# SCH_POTY_2026-03-09.net
KiCad netlist of a schematic drawn in EasyEDA
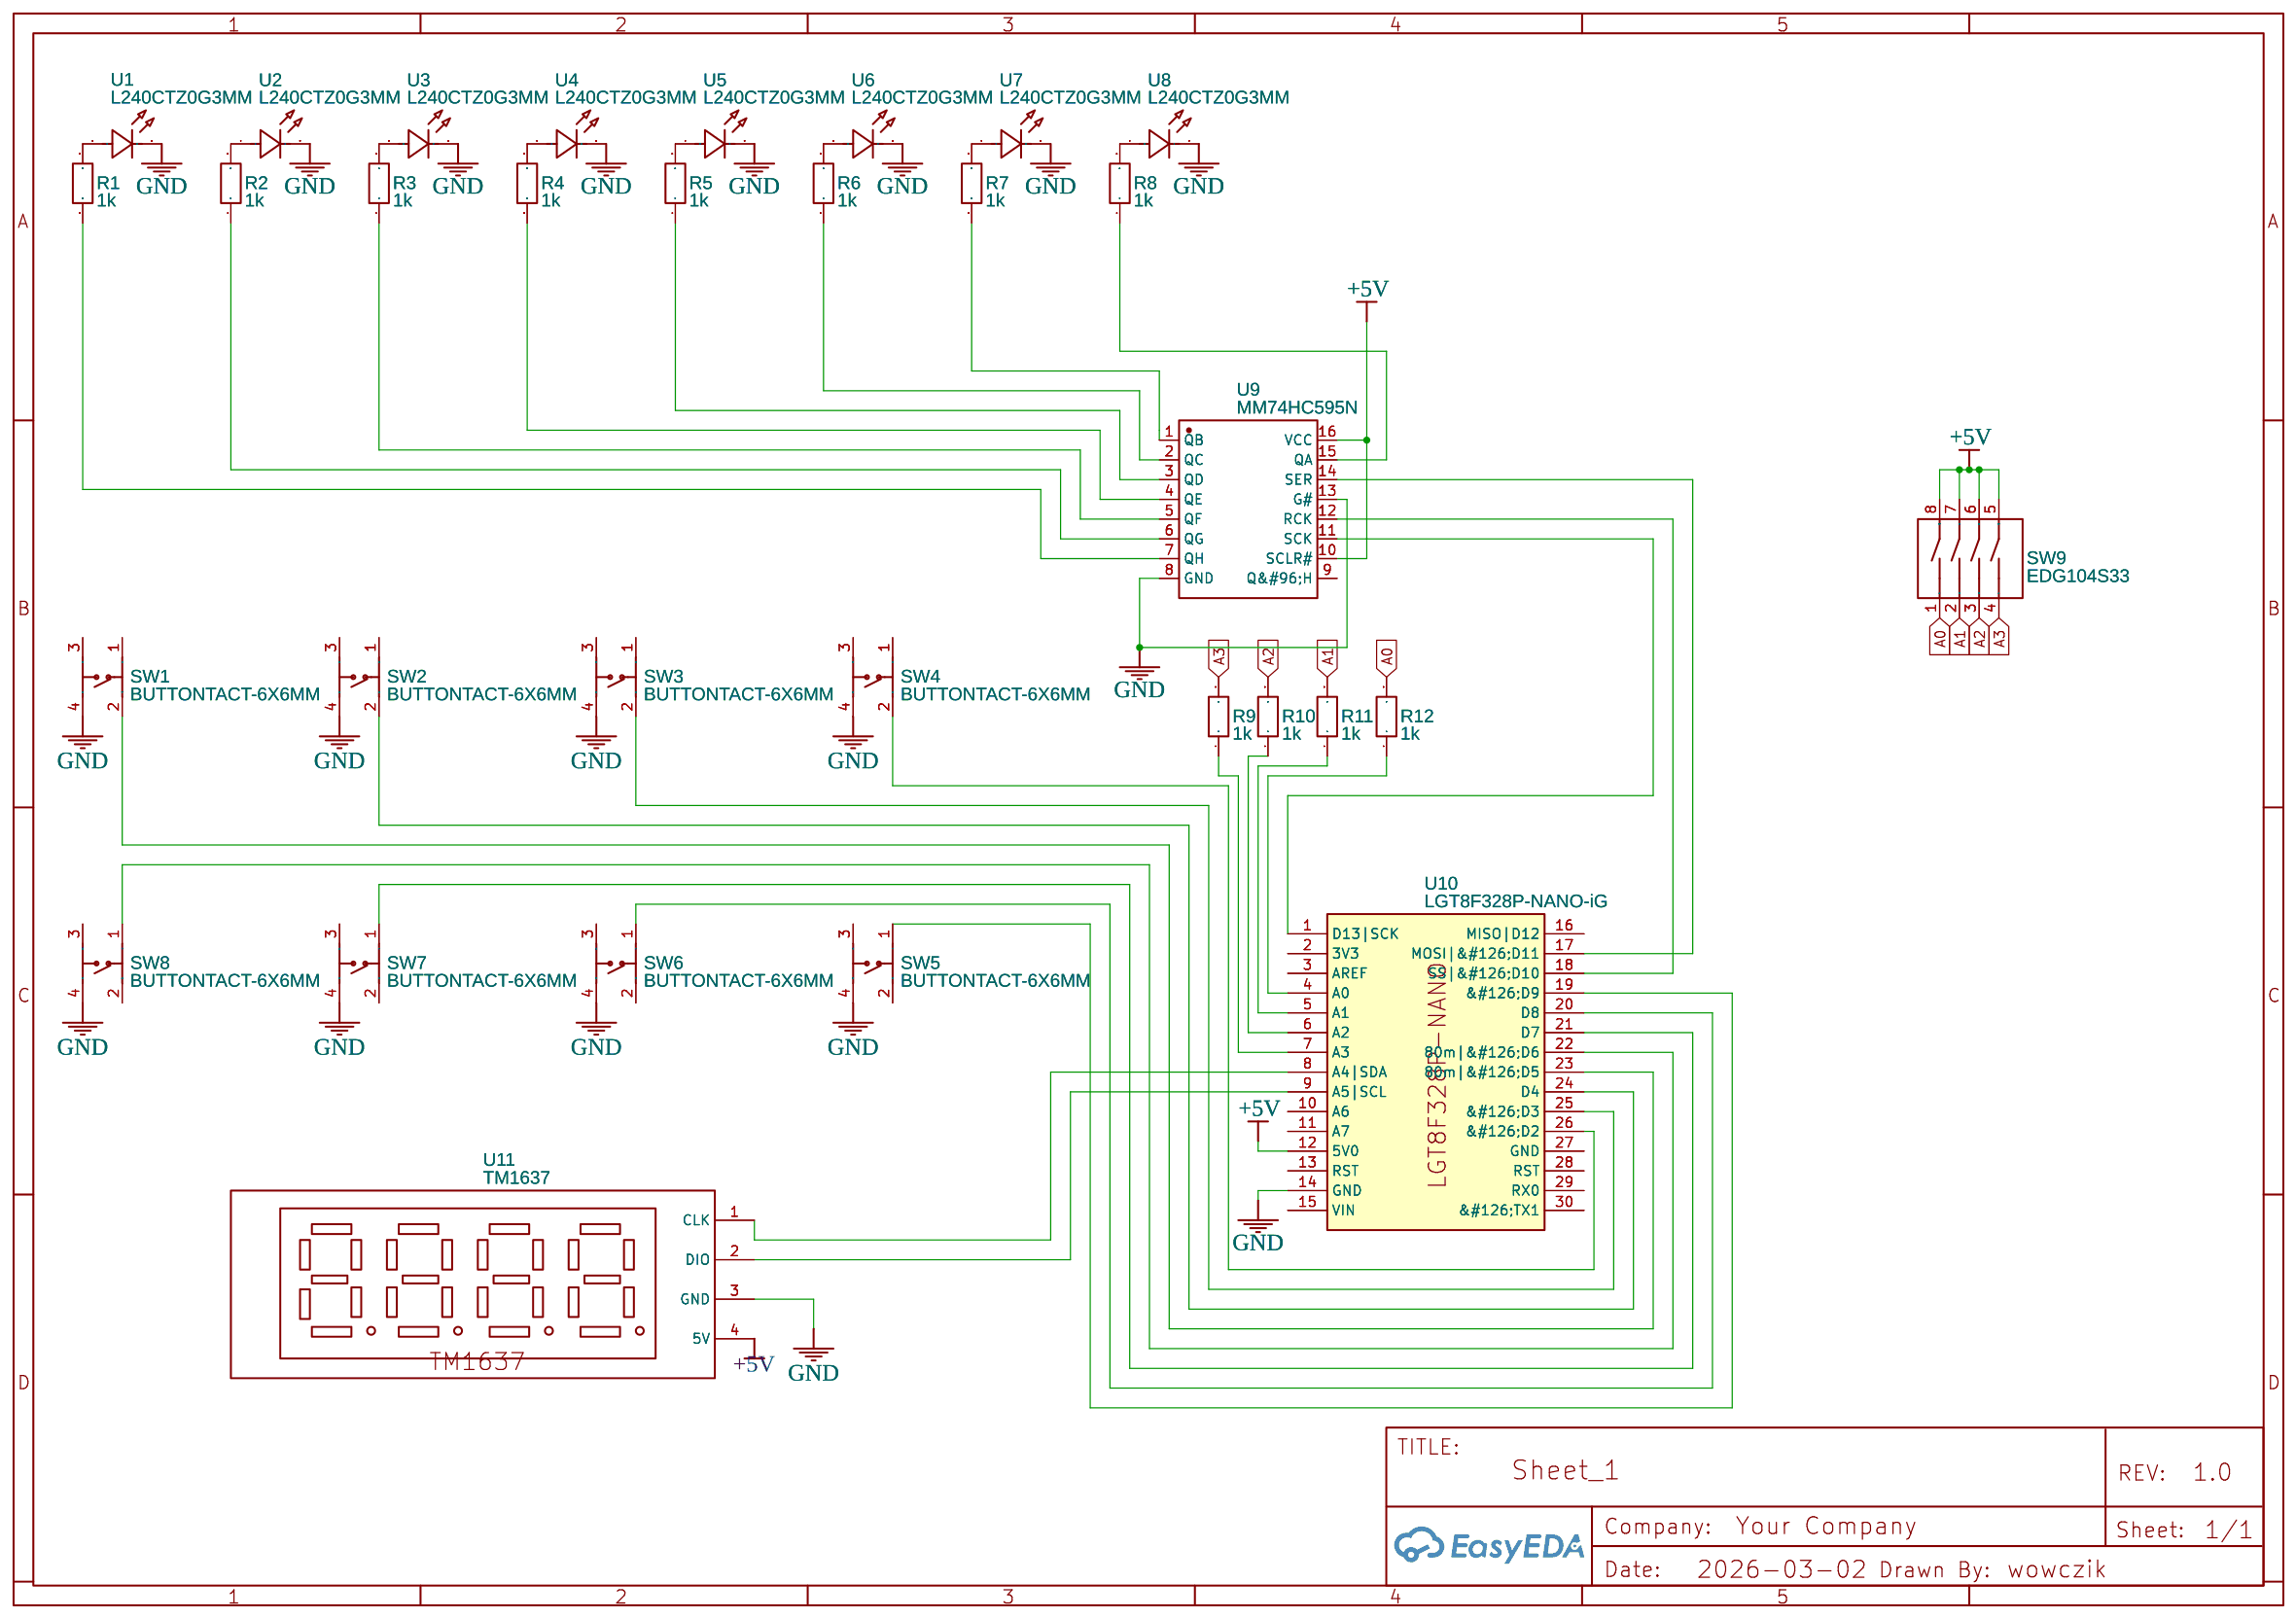
[diagram p0: schematic sheet]

(export (version "E")
  (design (tool "Eeschema 10.0.6"))
  (components
    (comp (ref "R1") (value "1k") (libsource (lib "") (part "R_AXIAL-0.3_EU")))
    (comp (ref "R2") (value "1k") (libsource (lib "") (part "R_AXIAL-0.3_EU")))
    (comp (ref "R3") (value "1k") (libsource (lib "") (part "R_AXIAL-0.3_EU")))
    (comp (ref "R4") (value "1k") (libsource (lib "") (part "R_AXIAL-0.3_EU")))
    (comp (ref "R5") (value "1k") (libsource (lib "") (part "R_AXIAL-0.3_EU")))
    (comp (ref "R6") (value "1k") (libsource (lib "") (part "R_AXIAL-0.3_EU")))
    (comp (ref "R7") (value "1k") (libsource (lib "") (part "R_AXIAL-0.3_EU")))
    (comp (ref "R8") (value "1k") (libsource (lib "") (part "R_AXIAL-0.3_EU")))
    (comp (ref "R9") (value "1k") (libsource (lib "") (part "R_0603_EU")))
    (comp (ref "R10") (value "1k") (libsource (lib "") (part "R_0603_EU")))
    (comp (ref "R11") (value "1k") (libsource (lib "") (part "R_0603_EU")))
    (comp (ref "R12") (value "1k") (libsource (lib "") (part "R_0603_EU")))
    (comp (ref "SW1")
      (value "BUTTONTACT-6X6MM")
      (fields (field (name "Manufacturer Part") "Buttontact-6x6mm"))
      (libsource (lib "") (part "BUTTONTACT-6X6MM"))
    )
    (comp (ref "SW2")
      (value "BUTTONTACT-6X6MM")
      (fields (field (name "Manufacturer Part") "Buttontact-6x6mm"))
      (libsource (lib "") (part "BUTTONTACT-6X6MM"))
    )
    (comp (ref "SW3")
      (value "BUTTONTACT-6X6MM")
      (fields (field (name "Manufacturer Part") "Buttontact-6x6mm"))
      (libsource (lib "") (part "BUTTONTACT-6X6MM"))
    )
    (comp (ref "SW4")
      (value "BUTTONTACT-6X6MM")
      (fields (field (name "Manufacturer Part") "Buttontact-6x6mm"))
      (libsource (lib "") (part "BUTTONTACT-6X6MM"))
    )
    (comp (ref "SW5")
      (value "BUTTONTACT-6X6MM")
      (fields (field (name "Manufacturer Part") "Buttontact-6x6mm"))
      (libsource (lib "") (part "BUTTONTACT-6X6MM"))
    )
    (comp (ref "SW6")
      (value "BUTTONTACT-6X6MM")
      (fields (field (name "Manufacturer Part") "Buttontact-6x6mm"))
      (libsource (lib "") (part "BUTTONTACT-6X6MM"))
    )
    (comp (ref "SW7")
      (value "BUTTONTACT-6X6MM")
      (fields (field (name "Manufacturer Part") "Buttontact-6x6mm"))
      (libsource (lib "") (part "BUTTONTACT-6X6MM"))
    )
    (comp (ref "SW8")
      (value "BUTTONTACT-6X6MM")
      (fields (field (name "Manufacturer Part") "Buttontact-6x6mm"))
      (libsource (lib "") (part "BUTTONTACT-6X6MM"))
    )
    (comp (ref "SW9")
      (value "EDG104S33")
      (fields (field (name "Manufacturer") "ECE(百容)"))
      (libsource (lib "") (part "EDG104S33"))
    )
    (comp (ref "U1") (value "L240CTZ0G3MM") (libsource (lib "") (part "L240CTZ0G3MM")))
    (comp (ref "U2") (value "L240CTZ0G3MM") (libsource (lib "") (part "L240CTZ0G3MM")))
    (comp (ref "U3") (value "L240CTZ0G3MM") (libsource (lib "") (part "L240CTZ0G3MM")))
    (comp (ref "U4") (value "L240CTZ0G3MM") (libsource (lib "") (part "L240CTZ0G3MM")))
    (comp (ref "U5") (value "L240CTZ0G3MM") (libsource (lib "") (part "L240CTZ0G3MM")))
    (comp (ref "U6") (value "L240CTZ0G3MM") (libsource (lib "") (part "L240CTZ0G3MM")))
    (comp (ref "U7") (value "L240CTZ0G3MM") (libsource (lib "") (part "L240CTZ0G3MM")))
    (comp (ref "U8") (value "L240CTZ0G3MM") (libsource (lib "") (part "L240CTZ0G3MM")))
    (comp (ref "U9")
      (value "MM74HC595N")
      (fields (field (name "Manufacturer") "onsemi(安森美)"))
      (libsource (lib "") (part "MM74HC595N"))
    )
    (comp (ref "U10") (value "LGT8F328P-NANO-iG") (libsource (lib "") (part "LGT8F328P-NANO-iG")))
    (comp (ref "U11") (value "TM1637") (libsource (lib "") (part "TM1637")))
  )
  (nets
    (net (code "1") (name "+5V") (class "Default")
      (node (ref "SW9") (pin "5") (pinfunction "5_5") (pintype "unspecified"))
      (node (ref "SW9") (pin "6") (pinfunction "6_6") (pintype "unspecified"))
      (node (ref "SW9") (pin "7") (pinfunction "7_7") (pintype "unspecified"))
      (node (ref "SW9") (pin "8") (pinfunction "8_8") (pintype "unspecified"))
      (node (ref "U10") (pin "12") (pinfunction "5V0_12") (pintype "unspecified"))
      (node (ref "U11") (pin "4") (pinfunction "5V_4") (pintype "unspecified"))
      (node (ref "U9") (pin "10") (pinfunction "SCLR#_10") (pintype "unspecified"))
      (node (ref "U9") (pin "16") (pinfunction "VCC_16") (pintype "unspecified"))
    )
    (net (code "2") (name "A0") (class "Default")
      (node (ref "R12") (pin "2") (pinfunction "2_2") (pintype "unspecified"))
      (node (ref "SW9") (pin "1") (pinfunction "1_1") (pintype "unspecified"))
    )
    (net (code "3") (name "A1") (class "Default")
      (node (ref "R11") (pin "2") (pinfunction "2_2") (pintype "unspecified"))
      (node (ref "SW9") (pin "2") (pinfunction "2_2") (pintype "unspecified"))
    )
    (net (code "4") (name "A2") (class "Default")
      (node (ref "R10") (pin "2") (pinfunction "2_2") (pintype "unspecified"))
      (node (ref "SW9") (pin "3") (pinfunction "3_3") (pintype "unspecified"))
    )
    (net (code "5") (name "A3") (class "Default")
      (node (ref "R9") (pin "2") (pinfunction "2_2") (pintype "unspecified"))
      (node (ref "SW9") (pin "4") (pinfunction "4_4") (pintype "unspecified"))
    )
    (net (code "6") (name "GND") (class "Default")
      (node (ref "SW1") (pin "4") (pinfunction "D_4") (pintype "unspecified"))
      (node (ref "SW2") (pin "4") (pinfunction "D_4") (pintype "unspecified"))
      (node (ref "SW3") (pin "4") (pinfunction "D_4") (pintype "unspecified"))
      (node (ref "SW4") (pin "4") (pinfunction "D_4") (pintype "unspecified"))
      (node (ref "SW5") (pin "4") (pinfunction "D_4") (pintype "unspecified"))
      (node (ref "SW6") (pin "4") (pinfunction "D_4") (pintype "unspecified"))
      (node (ref "SW7") (pin "4") (pinfunction "D_4") (pintype "unspecified"))
      (node (ref "SW8") (pin "4") (pinfunction "D_4") (pintype "unspecified"))
      (node (ref "U1") (pin "2") (pinfunction "K_2") (pintype "unspecified"))
      (node (ref "U10") (pin "14") (pinfunction "GND_14") (pintype "unspecified"))
      (node (ref "U11") (pin "3") (pinfunction "GND_3") (pintype "unspecified"))
      (node (ref "U2") (pin "2") (pinfunction "K_2") (pintype "unspecified"))
      (node (ref "U3") (pin "2") (pinfunction "K_2") (pintype "unspecified"))
      (node (ref "U4") (pin "2") (pinfunction "K_2") (pintype "unspecified"))
      (node (ref "U5") (pin "2") (pinfunction "K_2") (pintype "unspecified"))
      (node (ref "U6") (pin "2") (pinfunction "K_2") (pintype "unspecified"))
      (node (ref "U7") (pin "2") (pinfunction "K_2") (pintype "unspecified"))
      (node (ref "U8") (pin "2") (pinfunction "K_2") (pintype "unspecified"))
      (node (ref "U9") (pin "13") (pinfunction "G#_13") (pintype "unspecified"))
      (node (ref "U9") (pin "8") (pinfunction "GND_8") (pintype "unspecified"))
    )
    (net (code "7") (name "Net-(SW1-B)") (class "Default")
      (node (ref "SW1") (pin "2") (pinfunction "B_2") (pintype "unspecified"))
      (node (ref "U10") (pin "23") (pinfunction "80m|&#126;D5_23") (pintype "unspecified"))
    )
    (net (code "8") (name "Net-(SW2-B)") (class "Default")
      (node (ref "SW2") (pin "2") (pinfunction "B_2") (pintype "unspecified"))
      (node (ref "U10") (pin "24") (pinfunction "D4_24") (pintype "unspecified"))
    )
    (net (code "9") (name "Net-(SW3-B)") (class "Default")
      (node (ref "SW3") (pin "2") (pinfunction "B_2") (pintype "unspecified"))
      (node (ref "U10") (pin "25") (pinfunction "&#126;D3_25") (pintype "unspecified"))
    )
    (net (code "10") (name "Net-(SW4-B)") (class "Default")
      (node (ref "SW4") (pin "2") (pinfunction "B_2") (pintype "unspecified"))
      (node (ref "U10") (pin "26") (pinfunction "&#126;D2_26") (pintype "unspecified"))
    )
    (net (code "11") (name "Net-(SW5-A)") (class "Default")
      (node (ref "SW5") (pin "1") (pinfunction "A_1") (pintype "unspecified"))
      (node (ref "U10") (pin "19") (pinfunction "&#126;D9_19") (pintype "unspecified"))
    )
    (net (code "12") (name "Net-(SW6-A)") (class "Default")
      (node (ref "SW6") (pin "1") (pinfunction "A_1") (pintype "unspecified"))
      (node (ref "U10") (pin "20") (pinfunction "D8_20") (pintype "unspecified"))
    )
    (net (code "13") (name "Net-(SW7-A)") (class "Default")
      (node (ref "SW7") (pin "1") (pinfunction "A_1") (pintype "unspecified"))
      (node (ref "U10") (pin "21") (pinfunction "D7_21") (pintype "unspecified"))
    )
    (net (code "14") (name "Net-(SW8-A)") (class "Default")
      (node (ref "SW8") (pin "1") (pinfunction "A_1") (pintype "unspecified"))
      (node (ref "U10") (pin "22") (pinfunction "80m|&#126;D6_22") (pintype "unspecified"))
    )
    (net (code "15") (name "Net-(U1-A)") (class "Default")
      (node (ref "R1") (pin "2") (pinfunction "2_2") (pintype "unspecified"))
      (node (ref "U1") (pin "1") (pinfunction "A_1") (pintype "unspecified"))
    )
    (net (code "16") (name "Net-(U2-A)") (class "Default")
      (node (ref "R2") (pin "2") (pinfunction "2_2") (pintype "unspecified"))
      (node (ref "U2") (pin "1") (pinfunction "A_1") (pintype "unspecified"))
    )
    (net (code "17") (name "Net-(U3-A)") (class "Default")
      (node (ref "R3") (pin "2") (pinfunction "2_2") (pintype "unspecified"))
      (node (ref "U3") (pin "1") (pinfunction "A_1") (pintype "unspecified"))
    )
    (net (code "18") (name "Net-(U4-A)") (class "Default")
      (node (ref "R4") (pin "2") (pinfunction "2_2") (pintype "unspecified"))
      (node (ref "U4") (pin "1") (pinfunction "A_1") (pintype "unspecified"))
    )
    (net (code "19") (name "Net-(U5-A)") (class "Default")
      (node (ref "R5") (pin "2") (pinfunction "2_2") (pintype "unspecified"))
      (node (ref "U5") (pin "1") (pinfunction "A_1") (pintype "unspecified"))
    )
    (net (code "20") (name "Net-(U6-A)") (class "Default")
      (node (ref "R6") (pin "2") (pinfunction "2_2") (pintype "unspecified"))
      (node (ref "U6") (pin "1") (pinfunction "A_1") (pintype "unspecified"))
    )
    (net (code "21") (name "Net-(U7-A)") (class "Default")
      (node (ref "R7") (pin "2") (pinfunction "2_2") (pintype "unspecified"))
      (node (ref "U7") (pin "1") (pinfunction "A_1") (pintype "unspecified"))
    )
    (net (code "22") (name "Net-(U8-A)") (class "Default")
      (node (ref "R8") (pin "2") (pinfunction "2_2") (pintype "unspecified"))
      (node (ref "U8") (pin "1") (pinfunction "A_1") (pintype "unspecified"))
    )
    (net (code "23") (name "Net-(U9-QA)") (class "Default")
      (node (ref "R8") (pin "1") (pinfunction "1_1") (pintype "unspecified"))
      (node (ref "U9") (pin "15") (pinfunction "QA_15") (pintype "unspecified"))
    )
    (net (code "24") (name "Net-(U9-QB)") (class "Default")
      (node (ref "R7") (pin "1") (pinfunction "1_1") (pintype "unspecified"))
      (node (ref "U9") (pin "1") (pinfunction "QB_1") (pintype "unspecified"))
    )
    (net (code "25") (name "Net-(U9-QC)") (class "Default")
      (node (ref "R6") (pin "1") (pinfunction "1_1") (pintype "unspecified"))
      (node (ref "U9") (pin "2") (pinfunction "QC_2") (pintype "unspecified"))
    )
    (net (code "26") (name "Net-(U9-QD)") (class "Default")
      (node (ref "R5") (pin "1") (pinfunction "1_1") (pintype "unspecified"))
      (node (ref "U9") (pin "3") (pinfunction "QD_3") (pintype "unspecified"))
    )
    (net (code "27") (name "Net-(U9-QE)") (class "Default")
      (node (ref "R4") (pin "1") (pinfunction "1_1") (pintype "unspecified"))
      (node (ref "U9") (pin "4") (pinfunction "QE_4") (pintype "unspecified"))
    )
    (net (code "28") (name "Net-(U9-QF)") (class "Default")
      (node (ref "R3") (pin "1") (pinfunction "1_1") (pintype "unspecified"))
      (node (ref "U9") (pin "5") (pinfunction "QF_5") (pintype "unspecified"))
    )
    (net (code "29") (name "Net-(U9-QG)") (class "Default")
      (node (ref "R2") (pin "1") (pinfunction "1_1") (pintype "unspecified"))
      (node (ref "U9") (pin "6") (pinfunction "QG_6") (pintype "unspecified"))
    )
    (net (code "30") (name "Net-(U9-QH)") (class "Default")
      (node (ref "R1") (pin "1") (pinfunction "1_1") (pintype "unspecified"))
      (node (ref "U9") (pin "7") (pinfunction "QH_7") (pintype "unspecified"))
    )
    (net (code "31") (name "Net-(U10-A0)") (class "Default")
      (node (ref "R12") (pin "1") (pinfunction "1_1") (pintype "unspecified"))
      (node (ref "U10") (pin "4") (pinfunction "A0_4") (pintype "unspecified"))
    )
    (net (code "32") (name "Net-(U10-A1)") (class "Default")
      (node (ref "R11") (pin "1") (pinfunction "1_1") (pintype "unspecified"))
      (node (ref "U10") (pin "5") (pinfunction "A1_5") (pintype "unspecified"))
    )
    (net (code "33") (name "Net-(U10-A2)") (class "Default")
      (node (ref "R10") (pin "1") (pinfunction "1_1") (pintype "unspecified"))
      (node (ref "U10") (pin "6") (pinfunction "A2_6") (pintype "unspecified"))
    )
    (net (code "34") (name "Net-(U10-A3)") (class "Default")
      (node (ref "R9") (pin "1") (pinfunction "1_1") (pintype "unspecified"))
      (node (ref "U10") (pin "7") (pinfunction "A3_7") (pintype "unspecified"))
    )
    (net (code "35") (name "Net-(U10-A4|SDA)") (class "Default")
      (node (ref "U10") (pin "8") (pinfunction "A4|SDA_8") (pintype "unspecified"))
      (node (ref "U11") (pin "1") (pinfunction "CLK_1") (pintype "unspecified"))
    )
    (net (code "36") (name "Net-(U10-A5|SCL)") (class "Default")
      (node (ref "U10") (pin "9") (pinfunction "A5|SCL_9") (pintype "unspecified"))
      (node (ref "U11") (pin "2") (pinfunction "DIO_2") (pintype "unspecified"))
    )
    (net (code "37") (name "Net-(U10-D13|SCK)") (class "Default")
      (node (ref "U10") (pin "1") (pinfunction "D13|SCK_1") (pintype "unspecified"))
      (node (ref "U9") (pin "11") (pinfunction "SCK_11") (pintype "unspecified"))
    )
    (net (code "38") (name "Net-(U10-MOSI|&#126;D11)") (class "Default")
      (node (ref "U10") (pin "17") (pinfunction "MOSI|&#126;D11_17") (pintype "unspecified"))
      (node (ref "U9") (pin "14") (pinfunction "SER_14") (pintype "unspecified"))
    )
    (net (code "39") (name "Net-(U10-SS|&#126;D10)") (class "Default")
      (node (ref "U10") (pin "18") (pinfunction "SS|&#126;D10_18") (pintype "unspecified"))
      (node (ref "U9") (pin "12") (pinfunction "RCK_12") (pintype "unspecified"))
    )
    (net (code "40") (name "unconnected-(SW1-A-Pad1)") (class "Default")
      (node (ref "SW1") (pin "1") (pinfunction "A_1") (pintype "unspecified"))
    )
    (net (code "41") (name "unconnected-(SW1-C-Pad3)") (class "Default")
      (node (ref "SW1") (pin "3") (pinfunction "C_3") (pintype "unspecified"))
    )
    (net (code "42") (name "unconnected-(SW2-A-Pad1)") (class "Default")
      (node (ref "SW2") (pin "1") (pinfunction "A_1") (pintype "unspecified"))
    )
    (net (code "43") (name "unconnected-(SW2-C-Pad3)") (class "Default")
      (node (ref "SW2") (pin "3") (pinfunction "C_3") (pintype "unspecified"))
    )
    (net (code "44") (name "unconnected-(SW3-A-Pad1)") (class "Default")
      (node (ref "SW3") (pin "1") (pinfunction "A_1") (pintype "unspecified"))
    )
    (net (code "45") (name "unconnected-(SW3-C-Pad3)") (class "Default")
      (node (ref "SW3") (pin "3") (pinfunction "C_3") (pintype "unspecified"))
    )
    (net (code "46") (name "unconnected-(SW4-A-Pad1)") (class "Default")
      (node (ref "SW4") (pin "1") (pinfunction "A_1") (pintype "unspecified"))
    )
    (net (code "47") (name "unconnected-(SW4-C-Pad3)") (class "Default")
      (node (ref "SW4") (pin "3") (pinfunction "C_3") (pintype "unspecified"))
    )
    (net (code "48") (name "unconnected-(SW5-B-Pad2)") (class "Default")
      (node (ref "SW5") (pin "2") (pinfunction "B_2") (pintype "unspecified"))
    )
    (net (code "49") (name "unconnected-(SW5-C-Pad3)") (class "Default")
      (node (ref "SW5") (pin "3") (pinfunction "C_3") (pintype "unspecified"))
    )
    (net (code "50") (name "unconnected-(SW6-B-Pad2)") (class "Default")
      (node (ref "SW6") (pin "2") (pinfunction "B_2") (pintype "unspecified"))
    )
    (net (code "51") (name "unconnected-(SW6-C-Pad3)") (class "Default")
      (node (ref "SW6") (pin "3") (pinfunction "C_3") (pintype "unspecified"))
    )
    (net (code "52") (name "unconnected-(SW7-B-Pad2)") (class "Default")
      (node (ref "SW7") (pin "2") (pinfunction "B_2") (pintype "unspecified"))
    )
    (net (code "53") (name "unconnected-(SW7-C-Pad3)") (class "Default")
      (node (ref "SW7") (pin "3") (pinfunction "C_3") (pintype "unspecified"))
    )
    (net (code "54") (name "unconnected-(SW8-B-Pad2)") (class "Default")
      (node (ref "SW8") (pin "2") (pinfunction "B_2") (pintype "unspecified"))
    )
    (net (code "55") (name "unconnected-(SW8-C-Pad3)") (class "Default")
      (node (ref "SW8") (pin "3") (pinfunction "C_3") (pintype "unspecified"))
    )
    (net (code "56") (name "unconnected-(U9-Q&#96;H-Pad9)") (class "Default")
      (node (ref "U9") (pin "9") (pinfunction "Q&#96;H_9") (pintype "unspecified"))
    )
    (net (code "57") (name "unconnected-(U10-&#126;TX1-Pad30)") (class "Default")
      (node (ref "U10") (pin "30") (pinfunction "&#126;TX1_30") (pintype "unspecified"))
    )
    (net (code "58") (name "unconnected-(U10-3V3-Pad2)") (class "Default")
      (node (ref "U10") (pin "2") (pinfunction "3V3_2") (pintype "unspecified"))
    )
    (net (code "59") (name "unconnected-(U10-A6-Pad10)") (class "Default")
      (node (ref "U10") (pin "10") (pinfunction "A6_10") (pintype "unspecified"))
    )
    (net (code "60") (name "unconnected-(U10-A7-Pad11)") (class "Default")
      (node (ref "U10") (pin "11") (pinfunction "A7_11") (pintype "unspecified"))
    )
    (net (code "61") (name "unconnected-(U10-AREF-Pad3)") (class "Default")
      (node (ref "U10") (pin "3") (pinfunction "AREF_3") (pintype "unspecified"))
    )
    (net (code "62") (name "unconnected-(U10-GND-Pad27)") (class "Default")
      (node (ref "U10") (pin "27") (pinfunction "GND_27") (pintype "unspecified"))
    )
    (net (code "63") (name "unconnected-(U10-MISO|D12-Pad16)") (class "Default")
      (node (ref "U10") (pin "16") (pinfunction "MISO|D12_16") (pintype "unspecified"))
    )
    (net (code "64") (name "unconnected-(U10-RST-Pad13)") (class "Default")
      (node (ref "U10") (pin "13") (pinfunction "RST_13") (pintype "unspecified"))
    )
    (net (code "65") (name "unconnected-(U10-RST-Pad28)") (class "Default")
      (node (ref "U10") (pin "28") (pinfunction "RST_28") (pintype "unspecified"))
    )
    (net (code "66") (name "unconnected-(U10-RX0-Pad29)") (class "Default")
      (node (ref "U10") (pin "29") (pinfunction "RX0_29") (pintype "unspecified"))
    )
    (net (code "67") (name "unconnected-(U10-VIN-Pad15)") (class "Default")
      (node (ref "U10") (pin "15") (pinfunction "VIN_15") (pintype "unspecified"))
    )
  )
)
